# FPGA_Bank_IO.net
KiCad netlist of a schematic drawn in Altium Designer
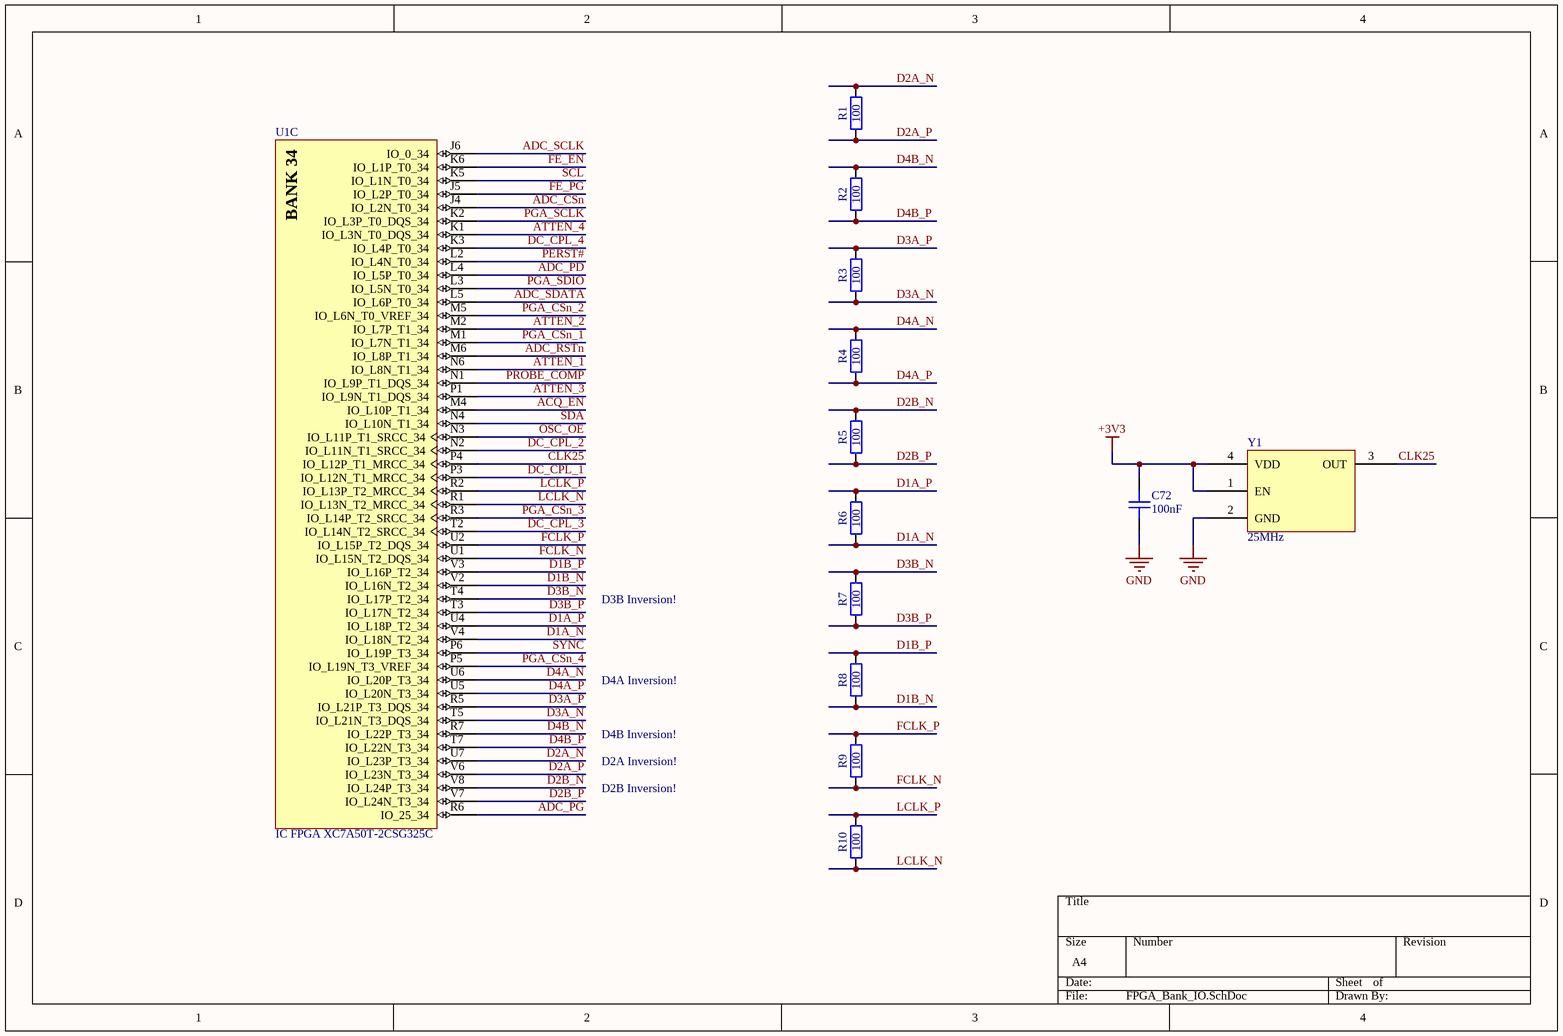
[diagram p0: FPGA_Bank_IO.SchDoc]

(export (version "E")
  (design (tool "Eeschema 10.0.6"))
  (components
    (comp (ref "C72")
      (value "100nF")
      (footprint "GEN_C_0402")
      (fields
        (field (name "HOUSE PART NUMBER") "C-100nF-0402-002")
        (field (name "MANUFACTURER") "Murata")
        (field (name "MANUFACTURER PART NUMBER") "GCM155R71C104KA55D")
      )
      (libsource (lib "DSO") (part "CAP 100nF 16V X7R 0402"))
    )
    (comp (ref "R1")
      (value "100")
      (footprint "GEN_R_0201")
      (fields
        (field (name "TOLERANCE") "1%")
        (field (name "HOUSE PART NUMBER") "R-100-0201-1%-001")
        (field (name "MANUFACTURER") "Yageo")
      )
      (libsource (lib "DSO") (part "RES 100 OHM 1% 1/20W 0201"))
    )
    (comp (ref "R2")
      (value "100")
      (footprint "GEN_R_0201")
      (fields
        (field (name "TOLERANCE") "1%")
        (field (name "HOUSE PART NUMBER") "R-100-0201-1%-001")
        (field (name "MANUFACTURER") "Yageo")
      )
      (libsource (lib "DSO") (part "RES 100 OHM 1% 1/20W 0201"))
    )
    (comp (ref "R3")
      (value "100")
      (footprint "GEN_R_0201")
      (fields
        (field (name "TOLERANCE") "1%")
        (field (name "HOUSE PART NUMBER") "R-100-0201-1%-001")
        (field (name "MANUFACTURER") "Yageo")
      )
      (libsource (lib "DSO") (part "RES 100 OHM 1% 1/20W 0201"))
    )
    (comp (ref "R4")
      (value "100")
      (footprint "GEN_R_0201")
      (fields
        (field (name "TOLERANCE") "1%")
        (field (name "HOUSE PART NUMBER") "R-100-0201-1%-001")
        (field (name "MANUFACTURER") "Yageo")
      )
      (libsource (lib "DSO") (part "RES 100 OHM 1% 1/20W 0201"))
    )
    (comp (ref "R5")
      (value "100")
      (footprint "GEN_R_0201")
      (fields
        (field (name "TOLERANCE") "1%")
        (field (name "HOUSE PART NUMBER") "R-100-0201-1%-001")
        (field (name "MANUFACTURER") "Yageo")
      )
      (libsource (lib "DSO") (part "RES 100 OHM 1% 1/20W 0201"))
    )
    (comp (ref "R6")
      (value "100")
      (footprint "GEN_R_0201")
      (fields
        (field (name "TOLERANCE") "1%")
        (field (name "HOUSE PART NUMBER") "R-100-0201-1%-001")
        (field (name "MANUFACTURER") "Yageo")
      )
      (libsource (lib "DSO") (part "RES 100 OHM 1% 1/20W 0201"))
    )
    (comp (ref "R7")
      (value "100")
      (footprint "GEN_R_0201")
      (fields
        (field (name "TOLERANCE") "1%")
        (field (name "HOUSE PART NUMBER") "R-100-0201-1%-001")
        (field (name "MANUFACTURER") "Yageo")
      )
      (libsource (lib "DSO") (part "RES 100 OHM 1% 1/20W 0201"))
    )
    (comp (ref "R8")
      (value "100")
      (footprint "GEN_R_0201")
      (fields
        (field (name "TOLERANCE") "1%")
        (field (name "HOUSE PART NUMBER") "R-100-0201-1%-001")
        (field (name "MANUFACTURER") "Yageo")
      )
      (libsource (lib "DSO") (part "RES 100 OHM 1% 1/20W 0201"))
    )
    (comp (ref "R9")
      (value "100")
      (footprint "GEN_R_0201")
      (fields
        (field (name "TOLERANCE") "1%")
        (field (name "HOUSE PART NUMBER") "R-100-0201-1%-001")
        (field (name "MANUFACTURER") "Yageo")
      )
      (libsource (lib "DSO") (part "RES 100 OHM 1% 1/20W 0201"))
    )
    (comp (ref "R10")
      (value "100")
      (footprint "GEN_R_0201")
      (fields
        (field (name "TOLERANCE") "1%")
        (field (name "HOUSE PART NUMBER") "R-100-0201-1%-001")
        (field (name "MANUFACTURER") "Yageo")
      )
      (libsource (lib "DSO") (part "RES 100 OHM 1% 1/20W 0201"))
    )
    (comp (ref "U1")
      (value "IC FPGA XC7A50T-2CSG325C")
      (footprint "XILINX_XC7A50T-2CSG325C")
      (description "Artix-7 FPGA, 150 User I/Os, 4 GTP, 324-Ball BGA, Speed Grade 2, Commercial Grade, Pb-Free")
      (fields (field (name "MANUFACTURER") "Xilinx") (field (name "HOUSE PART NUMBER") "XC7A50T-2CSG325C"))
      (libsource (lib "DSO") (part "IC FPGA XC7A50T-2CSG325C"))
    )
    (comp (ref "Y1")
      (value "25MHz")
      (footprint "ECS_TXO-2016")
      (fields
        (field (name "HOUSE PART NUMBER") "ECS-TXO-2016-33-250-TR")
        (field (name "MANUFACTURER") "ECS International")
      )
      (libsource (lib "DSO") (part "OSC 25MHz ECS-TXO-2016"))
    )
  )
  (nets
    (net (code "1") (name "+3V3") (class "Default")
      (node (ref "C72") (pin "1") (pinfunction "1_1") (pintype "passive"))
      (node (ref "Y1") (pin "1") (pinfunction "EN_1") (pintype "passive"))
      (node (ref "Y1") (pin "4") (pinfunction "VDD_4") (pintype "power_in"))
    )
    (net (code "2") (name "/ACQ_EN") (class "Default")
      (node (ref "U1") (pin "M4") (pinfunction "IO_L10P_T1_34_M4") (pintype "bidirectional"))
    )
    (net (code "3") (name "/ADC_CSn") (class "Default")
      (node (ref "U1") (pin "J4") (pinfunction "IO_L2N_T0_34_J4") (pintype "bidirectional"))
    )
    (net (code "4") (name "/ADC_PD") (class "Default")
      (node (ref "U1") (pin "L4") (pinfunction "IO_L5P_T0_34_L4") (pintype "bidirectional"))
    )
    (net (code "5") (name "/ADC_PG") (class "Default")
      (node (ref "U1") (pin "R6") (pinfunction "IO_25_34_R6") (pintype "bidirectional"))
    )
    (net (code "6") (name "/ADC_RSTn") (class "Default")
      (node (ref "U1") (pin "M6") (pinfunction "IO_L8P_T1_34_M6") (pintype "bidirectional"))
    )
    (net (code "7") (name "/ADC_SCLK") (class "Default")
      (node (ref "U1") (pin "J6") (pinfunction "IO_0_34_J6") (pintype "bidirectional"))
    )
    (net (code "8") (name "/ADC_SDATA") (class "Default")
      (node (ref "U1") (pin "L5") (pinfunction "IO_L6P_T0_34_L5") (pintype "bidirectional"))
    )
    (net (code "9") (name "/ATTEN_1") (class "Default")
      (node (ref "U1") (pin "N6") (pinfunction "IO_L8N_T1_34_N6") (pintype "bidirectional"))
    )
    (net (code "10") (name "/ATTEN_2") (class "Default")
      (node (ref "U1") (pin "M2") (pinfunction "IO_L7P_T1_34_M2") (pintype "bidirectional"))
    )
    (net (code "11") (name "/ATTEN_3") (class "Default")
      (node (ref "U1") (pin "P1") (pinfunction "IO_L9N_T1_DQS_34_P1") (pintype "bidirectional"))
    )
    (net (code "12") (name "/ATTEN_4") (class "Default")
      (node (ref "U1") (pin "K1") (pinfunction "IO_L3N_T0_DQS_34_K1") (pintype "bidirectional"))
    )
    (net (code "13") (name "/CLK25") (class "Default")
      (node (ref "U1") (pin "P4") (pinfunction "IO_L12P_T1_MRCC_34_P4") (pintype "bidirectional"))
      (node (ref "Y1") (pin "3") (pinfunction "OUT_3") (pintype "passive"))
    )
    (net (code "14") (name "/D1A_N") (class "Default")
      (node (ref "R6") (pin "1") (pinfunction "1_1") (pintype "passive"))
      (node (ref "U1") (pin "V4") (pinfunction "IO_L18N_T2_34_V4") (pintype "bidirectional"))
    )
    (net (code "15") (name "/D1A_P") (class "Default")
      (node (ref "R6") (pin "2") (pinfunction "2_2") (pintype "passive"))
      (node (ref "U1") (pin "U4") (pinfunction "IO_L18P_T2_34_U4") (pintype "bidirectional"))
    )
    (net (code "16") (name "/D1B_N") (class "Default")
      (node (ref "R8") (pin "1") (pinfunction "1_1") (pintype "passive"))
      (node (ref "U1") (pin "V2") (pinfunction "IO_L16N_T2_34_V2") (pintype "bidirectional"))
    )
    (net (code "17") (name "/D1B_P") (class "Default")
      (node (ref "R8") (pin "2") (pinfunction "2_2") (pintype "passive"))
      (node (ref "U1") (pin "V3") (pinfunction "IO_L16P_T2_34_V3") (pintype "bidirectional"))
    )
    (net (code "18") (name "/D2A_N") (class "Default")
      (node (ref "R1") (pin "2") (pinfunction "2_2") (pintype "passive"))
      (node (ref "U1") (pin "U7") (pinfunction "IO_L23P_T3_34_U7") (pintype "bidirectional"))
    )
    (net (code "19") (name "/D2A_P") (class "Default")
      (node (ref "R1") (pin "1") (pinfunction "1_1") (pintype "passive"))
      (node (ref "U1") (pin "V6") (pinfunction "IO_L23N_T3_34_V6") (pintype "bidirectional"))
    )
    (net (code "20") (name "/D2B_N") (class "Default")
      (node (ref "R5") (pin "2") (pinfunction "2_2") (pintype "passive"))
      (node (ref "U1") (pin "V8") (pinfunction "IO_L24P_T3_34_V8") (pintype "bidirectional"))
    )
    (net (code "21") (name "/D2B_P") (class "Default")
      (node (ref "R5") (pin "1") (pinfunction "1_1") (pintype "passive"))
      (node (ref "U1") (pin "V7") (pinfunction "IO_L24N_T3_34_V7") (pintype "bidirectional"))
    )
    (net (code "22") (name "/D3A_N") (class "Default")
      (node (ref "R3") (pin "1") (pinfunction "1_1") (pintype "passive"))
      (node (ref "U1") (pin "T5") (pinfunction "IO_L21N_T3_DQS_34_T5") (pintype "bidirectional"))
    )
    (net (code "23") (name "/D3A_P") (class "Default")
      (node (ref "R3") (pin "2") (pinfunction "2_2") (pintype "passive"))
      (node (ref "U1") (pin "R5") (pinfunction "IO_L21P_T3_DQS_34_R5") (pintype "bidirectional"))
    )
    (net (code "24") (name "/D3B_N") (class "Default")
      (node (ref "R7") (pin "2") (pinfunction "2_2") (pintype "passive"))
      (node (ref "U1") (pin "T4") (pinfunction "IO_L17P_T2_34_T4") (pintype "bidirectional"))
    )
    (net (code "25") (name "/D3B_P") (class "Default")
      (node (ref "R7") (pin "1") (pinfunction "1_1") (pintype "passive"))
      (node (ref "U1") (pin "T3") (pinfunction "IO_L17N_T2_34_T3") (pintype "bidirectional"))
    )
    (net (code "26") (name "/D4A_N") (class "Default")
      (node (ref "R4") (pin "2") (pinfunction "2_2") (pintype "passive"))
      (node (ref "U1") (pin "U6") (pinfunction "IO_L20P_T3_34_U6") (pintype "bidirectional"))
    )
    (net (code "27") (name "/D4A_P") (class "Default")
      (node (ref "R4") (pin "1") (pinfunction "1_1") (pintype "passive"))
      (node (ref "U1") (pin "U5") (pinfunction "IO_L20N_T3_34_U5") (pintype "bidirectional"))
    )
    (net (code "28") (name "/D4B_N") (class "Default")
      (node (ref "R2") (pin "2") (pinfunction "2_2") (pintype "passive"))
      (node (ref "U1") (pin "R7") (pinfunction "IO_L22P_T3_34_R7") (pintype "bidirectional"))
    )
    (net (code "29") (name "/D4B_P") (class "Default")
      (node (ref "R2") (pin "1") (pinfunction "1_1") (pintype "passive"))
      (node (ref "U1") (pin "T7") (pinfunction "IO_L22N_T3_34_T7") (pintype "bidirectional"))
    )
    (net (code "30") (name "/DC_CPL_1") (class "Default")
      (node (ref "U1") (pin "P3") (pinfunction "IO_L12N_T1_MRCC_34_P3") (pintype "bidirectional"))
    )
    (net (code "31") (name "/DC_CPL_2") (class "Default")
      (node (ref "U1") (pin "N2") (pinfunction "IO_L11N_T1_SRCC_34_N2") (pintype "bidirectional"))
    )
    (net (code "32") (name "/DC_CPL_3") (class "Default")
      (node (ref "U1") (pin "T2") (pinfunction "IO_L14N_T2_SRCC_34_T2") (pintype "bidirectional"))
    )
    (net (code "33") (name "/DC_CPL_4") (class "Default")
      (node (ref "U1") (pin "K3") (pinfunction "IO_L4P_T0_34_K3") (pintype "bidirectional"))
    )
    (net (code "34") (name "/FCLK_N") (class "Default")
      (node (ref "R9") (pin "1") (pinfunction "1_1") (pintype "passive"))
      (node (ref "U1") (pin "U1") (pinfunction "IO_L15N_T2_DQS_34_U1") (pintype "bidirectional"))
    )
    (net (code "35") (name "/FCLK_P") (class "Default")
      (node (ref "R9") (pin "2") (pinfunction "2_2") (pintype "passive"))
      (node (ref "U1") (pin "U2") (pinfunction "IO_L15P_T2_DQS_34_U2") (pintype "bidirectional"))
    )
    (net (code "36") (name "/FE_EN") (class "Default")
      (node (ref "U1") (pin "K6") (pinfunction "IO_L1P_T0_34_K6") (pintype "bidirectional"))
    )
    (net (code "37") (name "/FE_PG") (class "Default")
      (node (ref "U1") (pin "J5") (pinfunction "IO_L2P_T0_34_J5") (pintype "bidirectional"))
    )
    (net (code "38") (name "/LCLK_N") (class "Default")
      (node (ref "R10") (pin "1") (pinfunction "1_1") (pintype "passive"))
      (node (ref "U1") (pin "R1") (pinfunction "IO_L13N_T2_MRCC_34_R1") (pintype "bidirectional"))
    )
    (net (code "39") (name "/LCLK_P") (class "Default")
      (node (ref "R10") (pin "2") (pinfunction "2_2") (pintype "passive"))
      (node (ref "U1") (pin "R2") (pinfunction "IO_L13P_T2_MRCC_34_R2") (pintype "bidirectional"))
    )
    (net (code "40") (name "/OSC_OE") (class "Default")
      (node (ref "U1") (pin "N3") (pinfunction "IO_L11P_T1_SRCC_34_N3") (pintype "bidirectional"))
    )
    (net (code "41") (name "/PERST#") (class "Default")
      (node (ref "U1") (pin "L2") (pinfunction "IO_L4N_T0_34_L2") (pintype "bidirectional"))
    )
    (net (code "42") (name "/PGA_CSn_1") (class "Default")
      (node (ref "U1") (pin "M1") (pinfunction "IO_L7N_T1_34_M1") (pintype "bidirectional"))
    )
    (net (code "43") (name "/PGA_CSn_2") (class "Default")
      (node (ref "U1") (pin "M5") (pinfunction "IO_L6N_T0_VREF_34_M5") (pintype "bidirectional"))
    )
    (net (code "44") (name "/PGA_CSn_3") (class "Default")
      (node (ref "U1") (pin "R3") (pinfunction "IO_L14P_T2_SRCC_34_R3") (pintype "bidirectional"))
    )
    (net (code "45") (name "/PGA_CSn_4") (class "Default")
      (node (ref "U1") (pin "P5") (pinfunction "IO_L19N_T3_VREF_34_P5") (pintype "bidirectional"))
    )
    (net (code "46") (name "/PGA_SCLK") (class "Default")
      (node (ref "U1") (pin "K2") (pinfunction "IO_L3P_T0_DQS_34_K2") (pintype "bidirectional"))
    )
    (net (code "47") (name "/PGA_SDIO") (class "Default")
      (node (ref "U1") (pin "L3") (pinfunction "IO_L5N_T0_34_L3") (pintype "bidirectional"))
    )
    (net (code "48") (name "/PROBE_COMP") (class "Default")
      (node (ref "U1") (pin "N1") (pinfunction "IO_L9P_T1_DQS_34_N1") (pintype "bidirectional"))
    )
    (net (code "49") (name "/SCL") (class "Default")
      (node (ref "U1") (pin "K5") (pinfunction "IO_L1N_T0_34_K5") (pintype "bidirectional"))
    )
    (net (code "50") (name "/SDA") (class "Default")
      (node (ref "U1") (pin "N4") (pinfunction "IO_L10N_T1_34_N4") (pintype "bidirectional"))
    )
    (net (code "51") (name "/SYNC") (class "Default")
      (node (ref "U1") (pin "P6") (pinfunction "IO_L19P_T3_34_P6") (pintype "bidirectional"))
    )
    (net (code "52") (name "GND") (class "Default")
      (node (ref "C72") (pin "2") (pinfunction "2_2") (pintype "passive"))
      (node (ref "Y1") (pin "2") (pinfunction "GND_2") (pintype "power_in"))
    )
  )
)
